# STM32L052_Breadboard.net
KiCad netlist of a schematic drawn in EAGLE
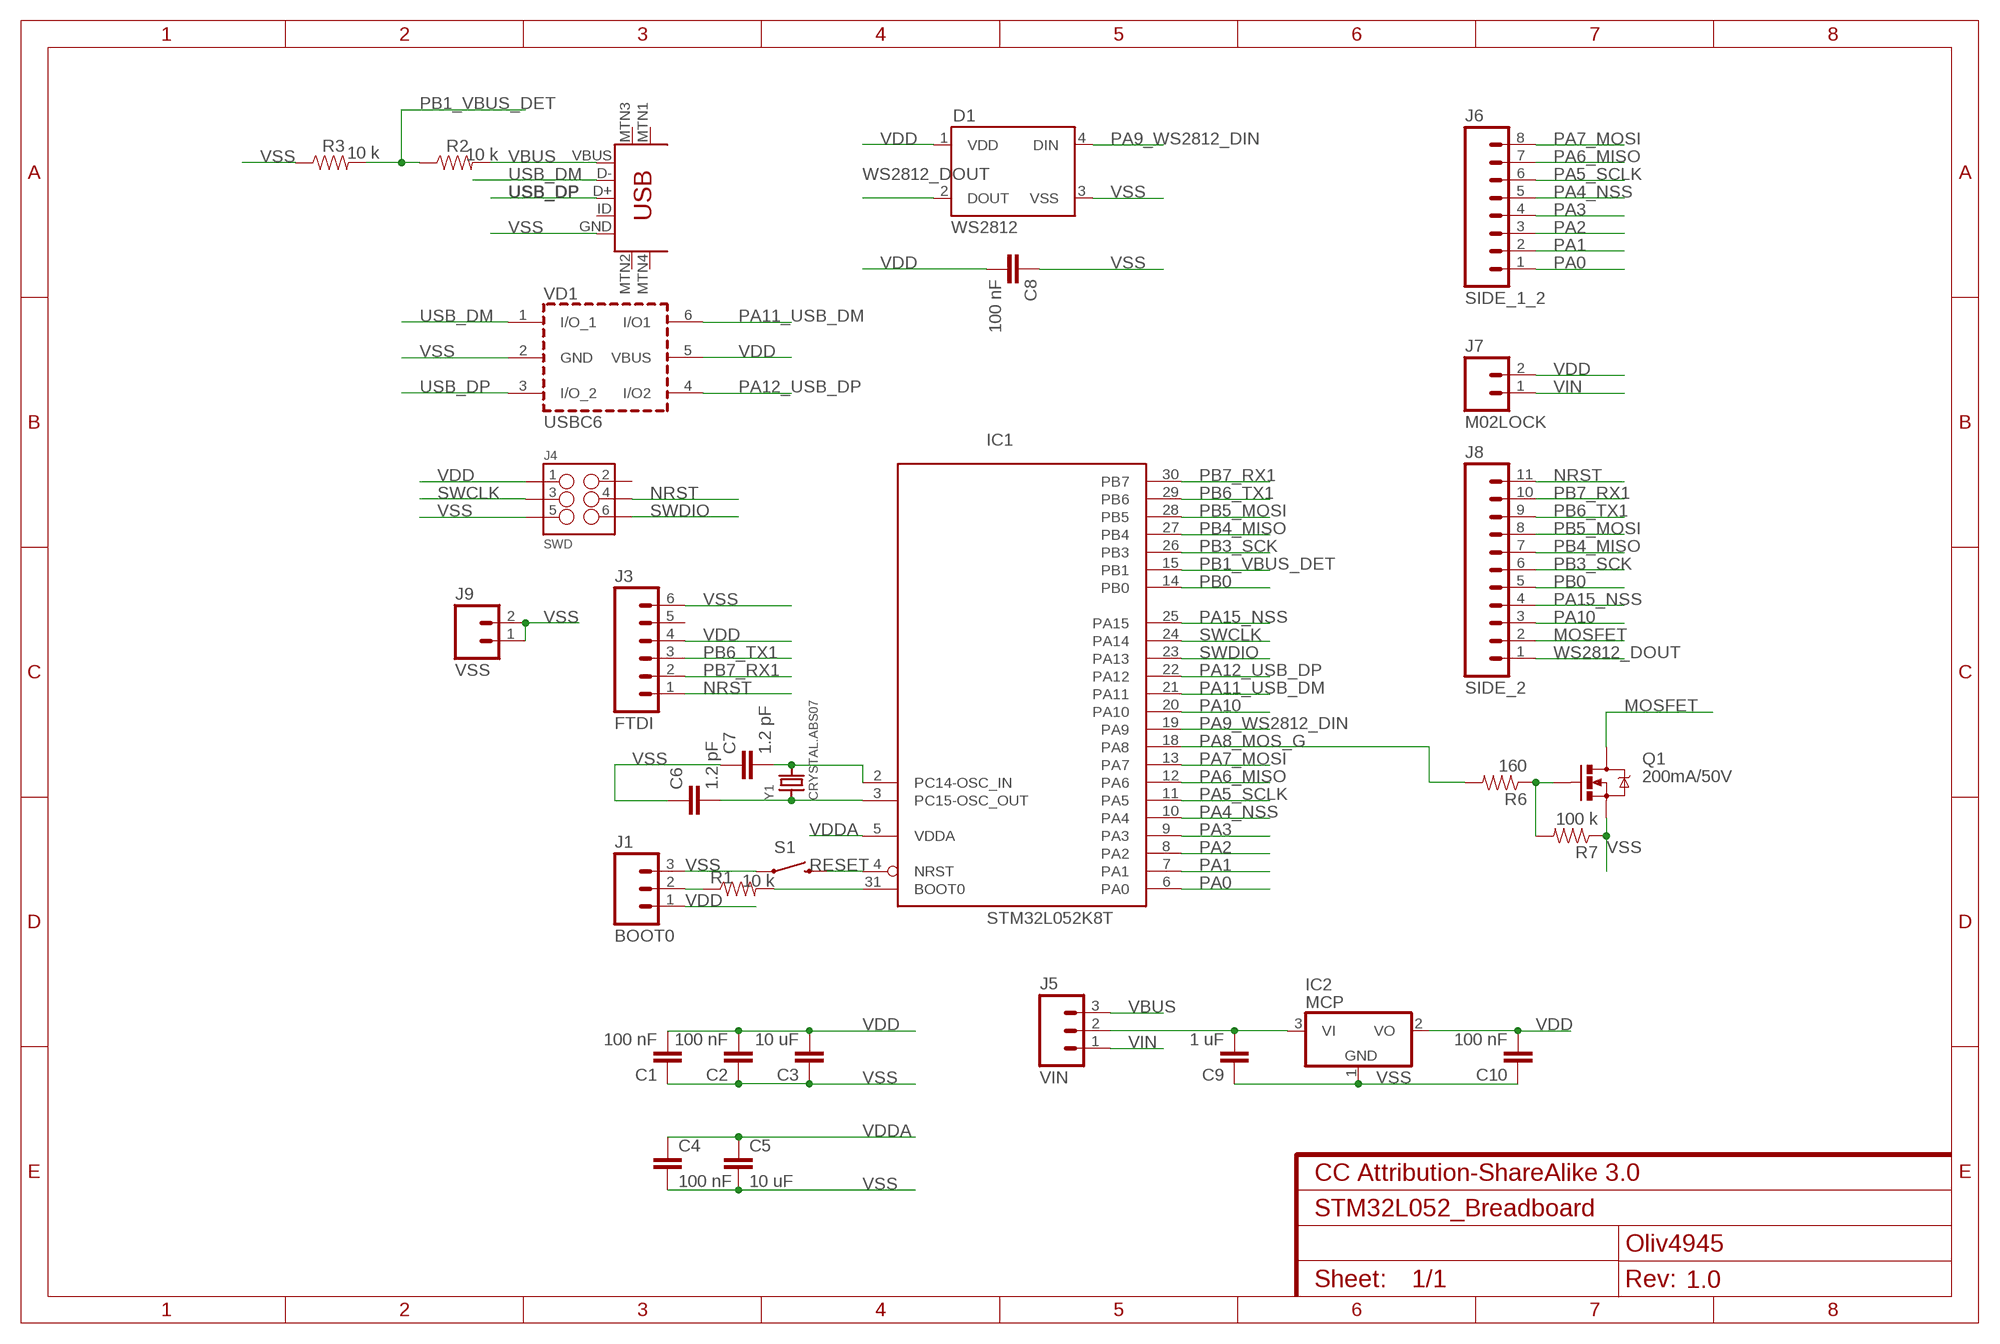
[diagram p0: schematic, sheet 1]

(export (version "E")
  (design (tool "Eeschema 10.0.6"))
  (components
    (comp (ref "C1")
      (value "100 nF")
      (footprint "eagle-import:0603-CAP")
      (libsource (lib "eagle-import") (part "CAP0603-CAP"))
    )
    (comp (ref "C2")
      (value "100 nF")
      (footprint "eagle-import:0603-CAP")
      (libsource (lib "eagle-import") (part "CAP0603-CAP"))
    )
    (comp (ref "C3")
      (value "10 uF")
      (footprint "eagle-import:0603-CAP")
      (libsource (lib "eagle-import") (part "CAP0603-CAP"))
    )
    (comp (ref "C4")
      (value "100 nF")
      (footprint "eagle-import:0603-CAP")
      (libsource (lib "eagle-import") (part "CAP0603-CAP"))
    )
    (comp (ref "C5")
      (value "10 uF")
      (footprint "eagle-import:0603-CAP")
      (libsource (lib "eagle-import") (part "CAP0603-CAP"))
    )
    (comp (ref "C6")
      (value "1.2 pF")
      (footprint "eagle-import:0603-CAP")
      (libsource (lib "eagle-import") (part "CAP0603-CAP"))
    )
    (comp (ref "C7")
      (value "1.2 pF")
      (footprint "eagle-import:0603-CAP")
      (libsource (lib "eagle-import") (part "CAP0603-CAP"))
    )
    (comp (ref "C8")
      (value "100 nF")
      (footprint "eagle-import:0603-CAP")
      (libsource (lib "eagle-import") (part "CAP0603-CAP"))
    )
    (comp (ref "C9")
      (value "1 uF")
      (footprint "eagle-import:0603-CAP")
      (libsource (lib "eagle-import") (part "CAP0603-CAP"))
    )
    (comp (ref "C10")
      (value "100 nF")
      (footprint "eagle-import:0603-CAP")
      (libsource (lib "eagle-import") (part "CAP0603-CAP"))
    )
    (comp (ref "D1")
      (value "WS2812")
      (footprint "eagle-import:WS2812B")
      (libsource (lib "eagle-import") (part "WS2812B"))
    )
    (comp (ref "IC1")
      (value "STM32L052K8T")
      (footprint "eagle-import:LQFP32")
      (libsource (lib "eagle-import") (part "STM32L052KT8"))
    )
    (comp (ref "IC2")
      (value "MCP")
      (footprint "eagle-import:SOT23")
      (libsource (lib "eagle-import") (part "MCP1703CB"))
    )
    (comp (ref "J1")
      (value "BOOT0")
      (footprint "eagle-import:1X03_LOCK")
      (libsource (lib "eagle-import") (part "M03LOCK"))
    )
    (comp (ref "J3")
      (value "FTDI")
      (footprint "eagle-import:1X06_LOCK")
      (libsource (lib "eagle-import") (part "M06LOCK"))
    )
    (comp (ref "J4")
      (value "SWD")
      (footprint "eagle-import:2X3")
      (libsource (lib "eagle-import") (part "M03X2FEMALE"))
    )
    (comp (ref "J5")
      (value "VIN")
      (footprint "eagle-import:1X03_LOCK")
      (libsource (lib "eagle-import") (part "M03LOCK"))
    )
    (comp (ref "J6")
      (value "SIDE_1_2")
      (footprint "eagle-import:1X08_LOCK")
      (libsource (lib "eagle-import") (part "M08LOCK"))
    )
    (comp (ref "J7")
      (value "M02LOCK")
      (footprint "eagle-import:1X02_LOCK")
      (libsource (lib "eagle-import") (part "M02LOCK"))
    )
    (comp (ref "J8")
      (value "SIDE_2")
      (footprint "eagle-import:1X11_LOCK")
      (libsource (lib "eagle-import") (part "M11LOCK"))
    )
    (comp (ref "J9")
      (value "VSS")
      (footprint "eagle-import:1X02_LOCK")
      (libsource (lib "eagle-import") (part "M02LOCK"))
    )
    (comp (ref "Q1")
      (value "200mA/50V")
      (footprint "eagle-import:SOT23-3")
      (libsource (lib "eagle-import") (part "MOSFET-NCHANNELBSS138"))
    )
    (comp (ref "R1")
      (value "10 k")
      (footprint "eagle-import:0603-RES")
      (libsource (lib "eagle-import") (part "RESISTOR0603"))
    )
    (comp (ref "R2")
      (value "10 k")
      (footprint "eagle-import:0603-RES")
      (libsource (lib "eagle-import") (part "RESISTOR0603"))
    )
    (comp (ref "R3")
      (value "10 k")
      (footprint "eagle-import:0603-RES")
      (libsource (lib "eagle-import") (part "RESISTOR0603"))
    )
    (comp (ref "R6")
      (value "160")
      (footprint "eagle-import:0805")
      (libsource (lib "eagle-import") (part "RESISTOR0805-RES"))
    )
    (comp (ref "R7")
      (value "100 k")
      (footprint "eagle-import:0805")
      (libsource (lib "eagle-import") (part "RESISTOR0805-RES"))
    )
    (comp (ref "S1")
      (value "RESET")
      (footprint "eagle-import:TACTILE-SWITCH-SMD")
      (libsource (lib "eagle-import") (part "SWITCH-MOMENTARY-2SMD"))
    )
    (comp (ref "U$1")
      (value "USB-MINIB-5PIN")
      (footprint "eagle-import:USB-MINIB")
      (libsource (lib "eagle-import") (part "USB-MINIB-5PIN"))
    )
    (comp (ref "VD1")
      (value "USBC6")
      (footprint "eagle-import:SOT-23-6L")
      (libsource (lib "eagle-import") (part "USBLC6-2SC6"))
    )
    (comp (ref "Y1")
      (value "CRYSTAL.ABS07")
      (footprint "eagle-import:ABS07")
      (libsource (lib "eagle-import") (part "CRYSTAL.ABS07"))
    )
  )
  (nets
    (net (code "1") (name "/MOSFET") (class "Default")
      (node (ref "J8") (pin "2") (pinfunction "2_2") (pintype "passive"))
      (node (ref "Q1") (pin "3") (pinfunction "D_3") (pintype "passive"))
    )
    (net (code "2") (name "/NRST") (class "Default")
      (node (ref "IC1") (pin "4") (pinfunction "NRST_4") (pintype "bidirectional"))
      (node (ref "J3") (pin "1") (pinfunction "1_1") (pintype "passive"))
      (node (ref "J4") (pin "4") (pinfunction "4_4") (pintype "bidirectional"))
      (node (ref "J8") (pin "11") (pinfunction "11_11") (pintype "passive"))
      (node (ref "S1") (pin "3") (pinfunction "2_3") (pintype "passive"))
    )
    (net (code "3") (name "/PA0") (class "Default")
      (node (ref "IC1") (pin "6") (pinfunction "PA0_6") (pintype "bidirectional"))
      (node (ref "J6") (pin "1") (pinfunction "1_1") (pintype "passive"))
    )
    (net (code "4") (name "/PA1") (class "Default")
      (node (ref "IC1") (pin "7") (pinfunction "PA1_7") (pintype "bidirectional"))
      (node (ref "J6") (pin "2") (pinfunction "2_2") (pintype "passive"))
    )
    (net (code "5") (name "/PA2") (class "Default")
      (node (ref "IC1") (pin "8") (pinfunction "PA2_8") (pintype "bidirectional"))
      (node (ref "J6") (pin "3") (pinfunction "3_3") (pintype "passive"))
    )
    (net (code "6") (name "/PA3") (class "Default")
      (node (ref "IC1") (pin "9") (pinfunction "PA3_9") (pintype "bidirectional"))
      (node (ref "J6") (pin "4") (pinfunction "4_4") (pintype "passive"))
    )
    (net (code "7") (name "/PA4_NSS") (class "Default")
      (node (ref "IC1") (pin "10") (pinfunction "PA4_10") (pintype "bidirectional"))
      (node (ref "J6") (pin "5") (pinfunction "5_5") (pintype "passive"))
    )
    (net (code "8") (name "/PA5_SCLK") (class "Default")
      (node (ref "IC1") (pin "11") (pinfunction "PA5_11") (pintype "bidirectional"))
      (node (ref "J6") (pin "6") (pinfunction "6_6") (pintype "passive"))
    )
    (net (code "9") (name "/PA6_MISO") (class "Default")
      (node (ref "IC1") (pin "12") (pinfunction "PA6_12") (pintype "bidirectional"))
      (node (ref "J6") (pin "7") (pinfunction "7_7") (pintype "passive"))
    )
    (net (code "10") (name "/PA7_MOSI") (class "Default")
      (node (ref "IC1") (pin "13") (pinfunction "PA7_13") (pintype "bidirectional"))
      (node (ref "J6") (pin "8") (pinfunction "8_8") (pintype "passive"))
    )
    (net (code "11") (name "/PA8_MOS_G") (class "Default")
      (node (ref "IC1") (pin "18") (pinfunction "PA8_18") (pintype "bidirectional"))
      (node (ref "R6") (pin "2") (pinfunction "2_2") (pintype "passive"))
    )
    (net (code "12") (name "/PA9_WS2812_DIN") (class "Default")
      (node (ref "D1") (pin "4") (pinfunction "DIN_4") (pintype "input"))
      (node (ref "IC1") (pin "19") (pinfunction "PA9_19") (pintype "bidirectional"))
    )
    (net (code "13") (name "/PA10") (class "Default")
      (node (ref "IC1") (pin "20") (pinfunction "PA10_20") (pintype "bidirectional"))
      (node (ref "J8") (pin "3") (pinfunction "3_3") (pintype "passive"))
    )
    (net (code "14") (name "/PA11_USB_DM") (class "Default")
      (node (ref "IC1") (pin "21") (pinfunction "PA11_21") (pintype "bidirectional"))
      (node (ref "VD1") (pin "6") (pinfunction "I/O1_6") (pintype "bidirectional"))
    )
    (net (code "15") (name "/PA12_USB_DP") (class "Default")
      (node (ref "IC1") (pin "22") (pinfunction "PA12_22") (pintype "bidirectional"))
      (node (ref "VD1") (pin "4") (pinfunction "I/O2_4") (pintype "bidirectional"))
    )
    (net (code "16") (name "/PA15_NSS") (class "Default")
      (node (ref "IC1") (pin "25") (pinfunction "PA15_25") (pintype "bidirectional"))
      (node (ref "J8") (pin "4") (pinfunction "4_4") (pintype "passive"))
    )
    (net (code "17") (name "/PB0") (class "Default")
      (node (ref "IC1") (pin "14") (pinfunction "PB0_14") (pintype "bidirectional"))
      (node (ref "J8") (pin "5") (pinfunction "5_5") (pintype "passive"))
    )
    (net (code "18") (name "/PB1_VBUS_DET") (class "Default")
      (node (ref "IC1") (pin "15") (pinfunction "PB1_15") (pintype "bidirectional"))
      (node (ref "R2") (pin "1") (pinfunction "1_1") (pintype "passive"))
      (node (ref "R3") (pin "2") (pinfunction "2_2") (pintype "passive"))
    )
    (net (code "19") (name "/PB3_SCK") (class "Default")
      (node (ref "IC1") (pin "26") (pinfunction "PB3_26") (pintype "bidirectional"))
      (node (ref "J8") (pin "6") (pinfunction "6_6") (pintype "passive"))
    )
    (net (code "20") (name "/PB4_MISO") (class "Default")
      (node (ref "IC1") (pin "27") (pinfunction "PB4_27") (pintype "bidirectional"))
      (node (ref "J8") (pin "7") (pinfunction "7_7") (pintype "passive"))
    )
    (net (code "21") (name "/PB5_MOSI") (class "Default")
      (node (ref "IC1") (pin "28") (pinfunction "PB5_28") (pintype "bidirectional"))
      (node (ref "J8") (pin "8") (pinfunction "8_8") (pintype "passive"))
    )
    (net (code "22") (name "/PB6_TX1") (class "Default")
      (node (ref "IC1") (pin "29") (pinfunction "PB6_29") (pintype "bidirectional"))
      (node (ref "J3") (pin "3") (pinfunction "3_3") (pintype "passive"))
      (node (ref "J8") (pin "9") (pinfunction "9_9") (pintype "passive"))
    )
    (net (code "23") (name "/PB7_RX1") (class "Default")
      (node (ref "IC1") (pin "30") (pinfunction "PB7_30") (pintype "bidirectional"))
      (node (ref "J3") (pin "2") (pinfunction "2_2") (pintype "passive"))
      (node (ref "J8") (pin "10") (pinfunction "10_10") (pintype "passive"))
    )
    (net (code "24") (name "/SWCLK") (class "Default")
      (node (ref "IC1") (pin "24") (pinfunction "PA14_24") (pintype "bidirectional"))
      (node (ref "J4") (pin "3") (pinfunction "3_3") (pintype "bidirectional"))
    )
    (net (code "25") (name "/SWDIO") (class "Default")
      (node (ref "IC1") (pin "23") (pinfunction "PA13_23") (pintype "bidirectional"))
      (node (ref "J4") (pin "6") (pinfunction "6_6") (pintype "bidirectional"))
    )
    (net (code "26") (name "/USB_DM") (class "Default")
      (node (ref "U$1") (pin "D-") (pinfunction "D-_D-") (pintype "bidirectional"))
      (node (ref "VD1") (pin "1") (pinfunction "I/O_1_1") (pintype "bidirectional"))
    )
    (net (code "27") (name "/USB_DP") (class "Default")
      (node (ref "U$1") (pin "D+") (pinfunction "D+_D+") (pintype "bidirectional"))
      (node (ref "VD1") (pin "3") (pinfunction "I/O_2_3") (pintype "bidirectional"))
    )
    (net (code "28") (name "/VBUS") (class "Default")
      (node (ref "J5") (pin "3") (pinfunction "3_3") (pintype "passive"))
      (node (ref "R2") (pin "2") (pinfunction "2_2") (pintype "passive"))
      (node (ref "U$1") (pin "VBUS") (pinfunction "VBUS_VBUS") (pintype "bidirectional"))
    )
    (net (code "29") (name "/VDD") (class "Default")
      (node (ref "C1") (pin "2") (pinfunction "2_2") (pintype "passive"))
      (node (ref "C10") (pin "2") (pinfunction "2_2") (pintype "passive"))
      (node (ref "C2") (pin "2") (pinfunction "2_2") (pintype "passive"))
      (node (ref "C3") (pin "2") (pinfunction "2_2") (pintype "passive"))
      (node (ref "C8") (pin "2") (pinfunction "2_2") (pintype "passive"))
      (node (ref "D1") (pin "1") (pinfunction "VDD_1") (pintype "power_in"))
      (node (ref "IC2") (pin "2") (pinfunction "VO_2") (pintype "passive"))
      (node (ref "J1") (pin "1") (pinfunction "1_1") (pintype "passive"))
      (node (ref "J3") (pin "4") (pinfunction "4_4") (pintype "passive"))
      (node (ref "J4") (pin "1") (pinfunction "1_1") (pintype "bidirectional"))
      (node (ref "J7") (pin "2") (pinfunction "2_2") (pintype "passive"))
      (node (ref "VD1") (pin "5") (pinfunction "VBUS_5") (pintype "bidirectional"))
    )
    (net (code "30") (name "/VDDA") (class "Default")
      (node (ref "C4") (pin "1") (pinfunction "1_1") (pintype "passive"))
      (node (ref "C5") (pin "1") (pinfunction "1_1") (pintype "passive"))
      (node (ref "IC1") (pin "5") (pinfunction "VDDA_5") (pintype "power_in"))
    )
    (net (code "31") (name "/VIN") (class "Default")
      (node (ref "J5") (pin "1") (pinfunction "1_1") (pintype "passive"))
      (node (ref "J7") (pin "1") (pinfunction "1_1") (pintype "passive"))
    )
    (net (code "32") (name "/VSS") (class "Default")
      (node (ref "C1") (pin "1") (pinfunction "1_1") (pintype "passive"))
      (node (ref "C10") (pin "1") (pinfunction "1_1") (pintype "passive"))
      (node (ref "C2") (pin "1") (pinfunction "1_1") (pintype "passive"))
      (node (ref "C3") (pin "1") (pinfunction "1_1") (pintype "passive"))
      (node (ref "C4") (pin "2") (pinfunction "2_2") (pintype "passive"))
      (node (ref "C5") (pin "2") (pinfunction "2_2") (pintype "passive"))
      (node (ref "C6") (pin "1") (pinfunction "1_1") (pintype "passive"))
      (node (ref "C7") (pin "1") (pinfunction "1_1") (pintype "passive"))
      (node (ref "C8") (pin "1") (pinfunction "1_1") (pintype "passive"))
      (node (ref "C9") (pin "1") (pinfunction "1_1") (pintype "passive"))
      (node (ref "D1") (pin "3") (pinfunction "VSS_3") (pintype "power_in"))
      (node (ref "IC2") (pin "1") (pinfunction "GND_1") (pintype "passive"))
      (node (ref "J1") (pin "3") (pinfunction "3_3") (pintype "passive"))
      (node (ref "J3") (pin "6") (pinfunction "6_6") (pintype "passive"))
      (node (ref "J4") (pin "5") (pinfunction "5_5") (pintype "bidirectional"))
      (node (ref "J9") (pin "1") (pinfunction "1_1") (pintype "passive"))
      (node (ref "J9") (pin "2") (pinfunction "2_2") (pintype "passive"))
      (node (ref "Q1") (pin "2") (pinfunction "S_2") (pintype "passive"))
      (node (ref "R3") (pin "1") (pinfunction "1_1") (pintype "passive"))
      (node (ref "R7") (pin "1") (pinfunction "1_1") (pintype "passive"))
      (node (ref "S1") (pin "1") (pinfunction "1_1") (pintype "passive"))
      (node (ref "U$1") (pin "GND") (pinfunction "GND_GND") (pintype "bidirectional"))
      (node (ref "VD1") (pin "2") (pinfunction "GND_2") (pintype "bidirectional"))
    )
    (net (code "33") (name "/WS2812_DOUT") (class "Default")
      (node (ref "D1") (pin "2") (pinfunction "DOUT_2") (pintype "output"))
      (node (ref "J8") (pin "1") (pinfunction "1_1") (pintype "passive"))
    )
    (net (code "34") (name "Net-(IC1A-BOOT0)") (class "Default")
      (node (ref "IC1") (pin "31") (pinfunction "BOOT0_31") (pintype "input"))
      (node (ref "R1") (pin "2") (pinfunction "2_2") (pintype "passive"))
    )
    (net (code "35") (name "Net-(IC1A-PC14-OSC_IN)") (class "Default")
      (node (ref "C7") (pin "2") (pinfunction "2_2") (pintype "passive"))
      (node (ref "IC1") (pin "2") (pinfunction "PC14-OSC_IN_2") (pintype "bidirectional"))
      (node (ref "Y1") (pin "2") (pinfunction "2_2") (pintype "passive"))
    )
    (net (code "36") (name "Net-(IC1A-PC15-OSC_OUT)") (class "Default")
      (node (ref "C6") (pin "2") (pinfunction "2_2") (pintype "passive"))
      (node (ref "IC1") (pin "3") (pinfunction "PC15-OSC_OUT_3") (pintype "bidirectional"))
      (node (ref "Y1") (pin "1") (pinfunction "1_1") (pintype "passive"))
    )
    (net (code "37") (name "Net-(IC2-VI)") (class "Default")
      (node (ref "C9") (pin "2") (pinfunction "2_2") (pintype "passive"))
      (node (ref "IC2") (pin "3") (pinfunction "VI_3") (pintype "input"))
      (node (ref "J5") (pin "2") (pinfunction "2_2") (pintype "passive"))
    )
    (net (code "38") (name "Net-(J1-Pad2)") (class "Default")
      (node (ref "J1") (pin "2") (pinfunction "2_2") (pintype "passive"))
      (node (ref "R1") (pin "1") (pinfunction "1_1") (pintype "passive"))
    )
    (net (code "39") (name "Net-(Q1-G)") (class "Default")
      (node (ref "Q1") (pin "1") (pinfunction "G_1") (pintype "passive"))
      (node (ref "R6") (pin "1") (pinfunction "1_1") (pintype "passive"))
      (node (ref "R7") (pin "2") (pinfunction "2_2") (pintype "passive"))
    )
    (net (code "40") (name "unconnected-(J3-Pad5)") (class "Default")
      (node (ref "J3") (pin "5") (pinfunction "5_5") (pintype "passive"))
    )
    (net (code "41") (name "unconnected-(J4-Pad2)") (class "Default")
      (node (ref "J4") (pin "2") (pinfunction "2_2") (pintype "bidirectional"))
    )
    (net (code "42") (name "unconnected-(U$1-MTN1-PadMTN3)") (class "Default")
      (node (ref "U$1") (pin "MTN3") (pinfunction "MTN1_MTN3") (pintype "bidirectional"))
    )
    (net (code "43") (name "unconnected-(U$1-MTN2-PadMTN1)") (class "Default")
      (node (ref "U$1") (pin "MTN1") (pinfunction "MTN2_MTN1") (pintype "bidirectional"))
    )
    (net (code "44") (name "unconnected-(U$1-MTN3-PadMTN2)") (class "Default")
      (node (ref "U$1") (pin "MTN2") (pinfunction "MTN3_MTN2") (pintype "bidirectional"))
    )
    (net (code "45") (name "unconnected-(U$1-PadID)") (class "Default")
      (node (ref "U$1") (pin "ID") (pinfunction "ID_ID") (pintype "bidirectional"))
    )
    (net (code "46") (name "unconnected-(U$1-PadMTN4)") (class "Default")
      (node (ref "U$1") (pin "MTN4") (pinfunction "MTN4_MTN4") (pintype "bidirectional"))
    )
  )
)
